# prototype01.net
KiCad netlist of a schematic drawn in EAGLE
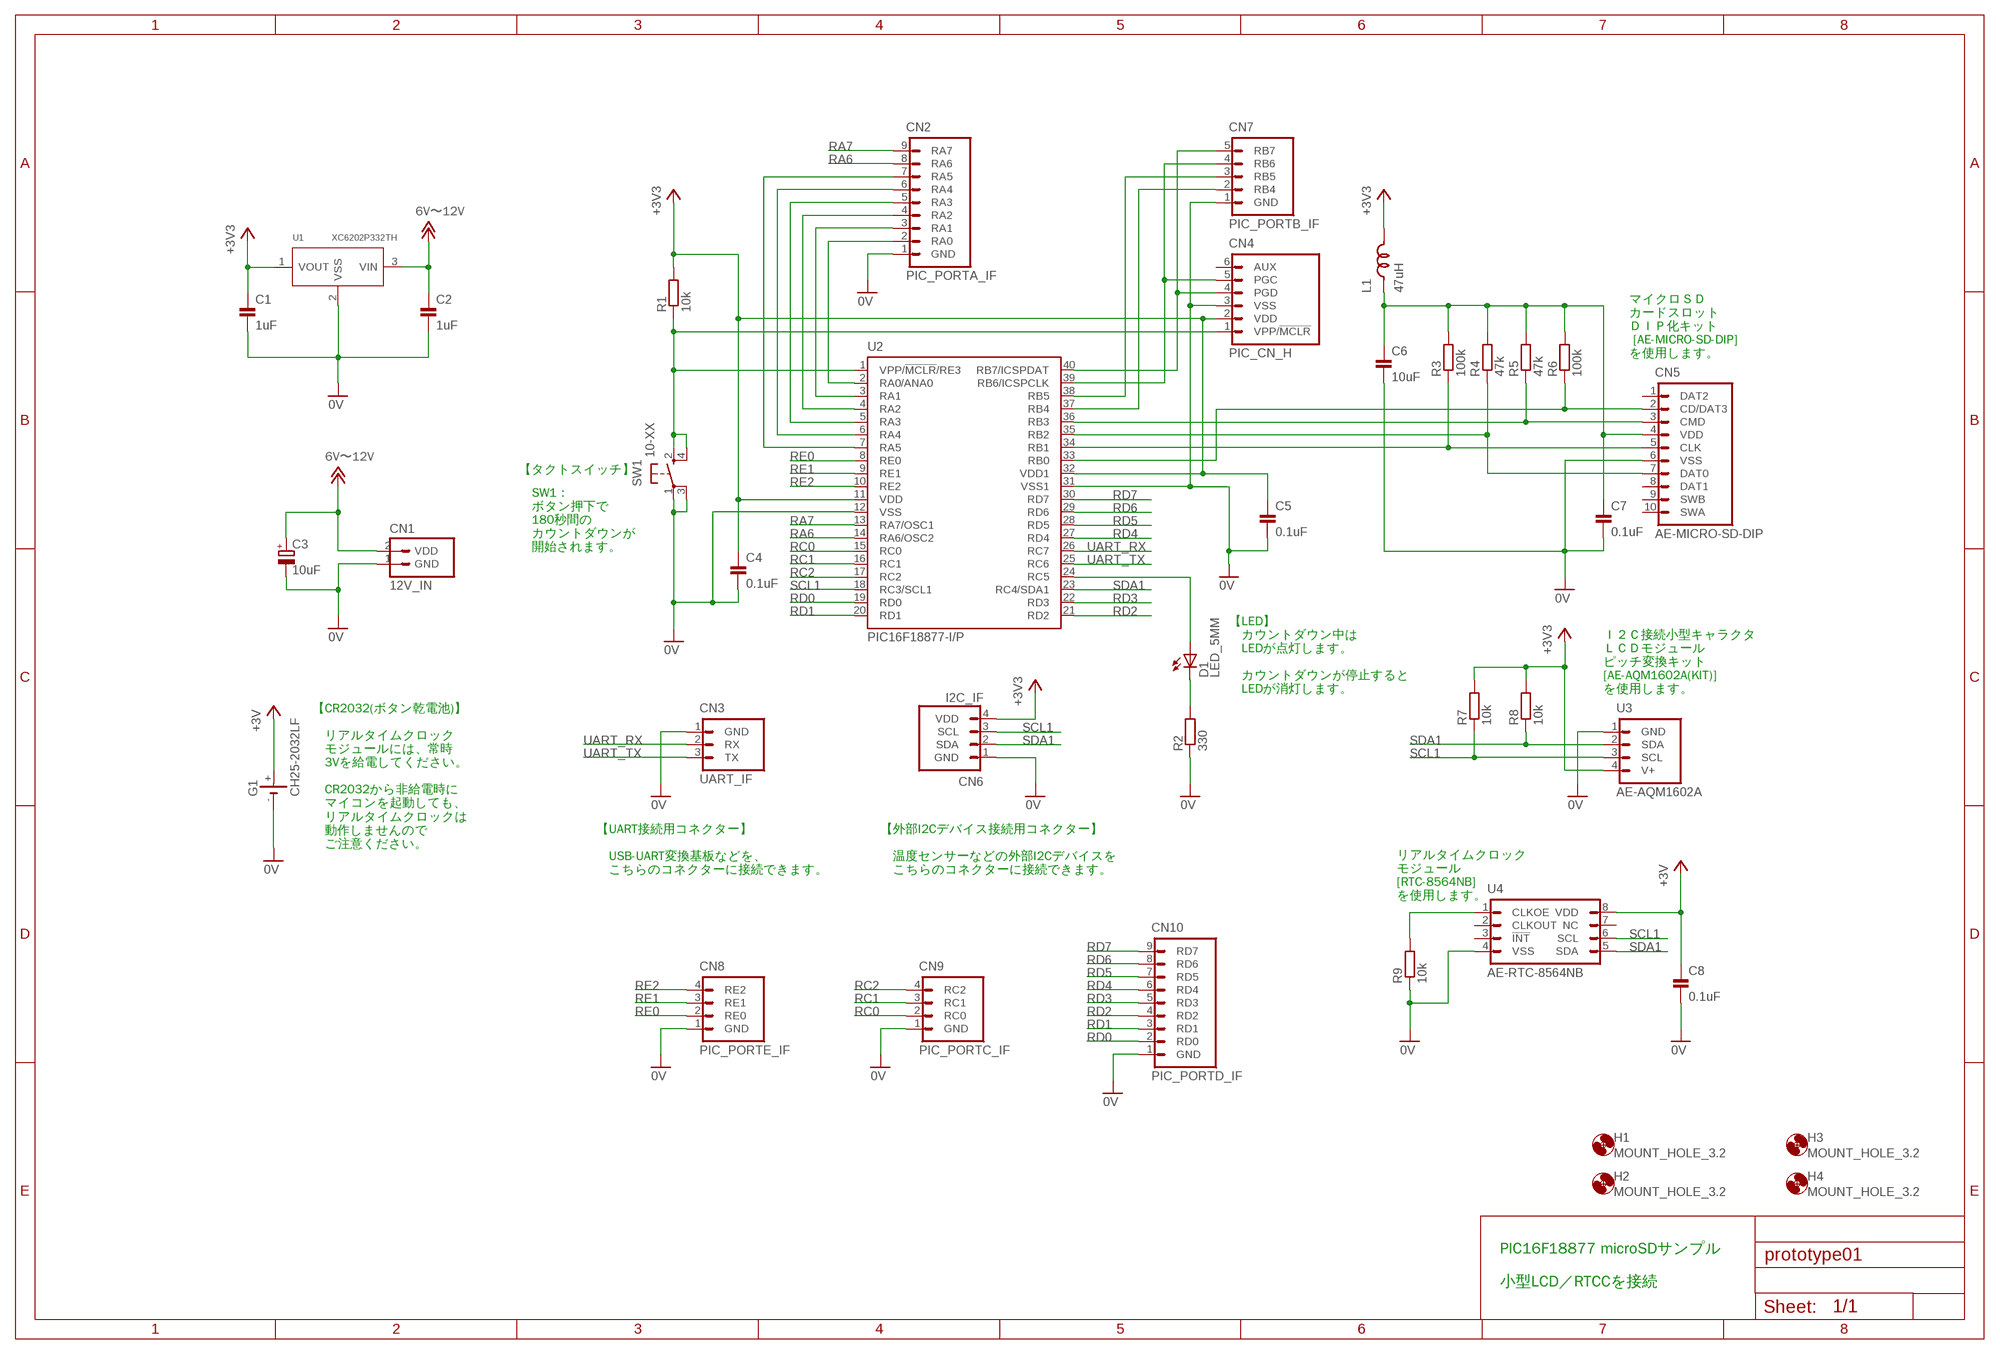
[diagram p0: schematic, sheet 1]

(export (version "E")
  (design (tool "Eeschema 10.0.6"))
  (components
    (comp (ref "C1")
      (value "1uF")
      (footprint "eagle-import:CAP_100MIL")
      (libsource (lib "eagle-import") (part "CAP_100MIL"))
    )
    (comp (ref "C2")
      (value "1uF")
      (footprint "eagle-import:CAP_100MIL")
      (libsource (lib "eagle-import") (part "CAP_100MIL"))
    )
    (comp (ref "C3")
      (value "10uF")
      (footprint "eagle-import:ELECAP_D5_100MIL")
      (libsource (lib "eagle-import") (part "ELECAP_D5_100MIL"))
    )
    (comp (ref "C4")
      (value "0.1uF")
      (footprint "eagle-import:CAP_100MIL")
      (libsource (lib "eagle-import") (part "CAP_100MIL"))
    )
    (comp (ref "C5")
      (value "0.1uF")
      (footprint "eagle-import:CAP_100MIL")
      (libsource (lib "eagle-import") (part "CAP_100MIL"))
    )
    (comp (ref "C6")
      (value "10uF")
      (footprint "eagle-import:CAP_100MIL")
      (libsource (lib "eagle-import") (part "CAP_100MIL"))
    )
    (comp (ref "C7")
      (value "0.1uF")
      (footprint "eagle-import:CAP_100MIL")
      (libsource (lib "eagle-import") (part "CAP_100MIL"))
    )
    (comp (ref "C8")
      (value "0.1uF")
      (footprint "eagle-import:CAP_100MIL")
      (libsource (lib "eagle-import") (part "CAP_100MIL"))
    )
    (comp (ref "CN1")
      (value "12V_IN")
      (footprint "eagle-import:HEADER_2PIN_POWER_IF")
      (libsource (lib "eagle-import") (part "POWER_IF"))
    )
    (comp (ref "CN2")
      (value "PIC_PORTA_IF")
      (footprint "eagle-import:PIC_PORTA_IF_9PIN")
      (libsource (lib "eagle-import") (part "PIC_PORTA_IF"))
    )
    (comp (ref "CN3")
      (value "UART_IF")
      (footprint "eagle-import:UART_IF_3PIN")
      (libsource (lib "eagle-import") (part "UART_IF"))
    )
    (comp (ref "CN4")
      (value "PIC_CN_H")
      (footprint "eagle-import:HEADER_6PIN")
      (libsource (lib "eagle-import") (part "PIC_CN_H"))
    )
    (comp (ref "CN5")
      (value "AE-MICRO-SD-DIP")
      (footprint "eagle-import:AE-MICRO-SD-DIP")
      (libsource (lib "eagle-import") (part "AE-MICRO-SD-DIP"))
    )
    (comp (ref "CN6")
      (value "I2C_IF")
      (footprint "eagle-import:I2C_IF_4PIN")
      (libsource (lib "eagle-import") (part "I2C_IF"))
    )
    (comp (ref "CN7")
      (value "PIC_PORTB_IF")
      (footprint "eagle-import:PIC_PORTB_IF_5PIN")
      (libsource (lib "eagle-import") (part "PIC_PORTB_IF"))
    )
    (comp (ref "CN8")
      (value "PIC_PORTE_IF")
      (footprint "eagle-import:PIC_PORTE_IF_4PIN")
      (libsource (lib "eagle-import") (part "PIC_PORTE_IF"))
    )
    (comp (ref "CN9")
      (value "PIC_PORTC_IF")
      (footprint "eagle-import:PIC_PORTC_IF_4PIN")
      (libsource (lib "eagle-import") (part "PIC_PORTC_IF"))
    )
    (comp (ref "CN10")
      (value "PIC_PORTD_IF")
      (footprint "eagle-import:PIC_PORTD_IF_9PIN")
      (libsource (lib "eagle-import") (part "PIC_PORTD_IF"))
    )
    (comp (ref "D1")
      (value "LED_5MM")
      (footprint "eagle-import:LED5MM")
      (libsource (lib "eagle-import") (part "LED_5MM"))
    )
    (comp (ref "G1")
      (value "CH25-2032LF")
      (footprint "eagle-import:CH25-2032LF")
      (libsource (lib "eagle-import") (part "CH25-2032LF"))
    )
    (comp (ref "H1")
      (value "MOUNT_HOLE_3.2")
      (footprint "eagle-import:3,2")
      (libsource (lib "eagle-import") (part "MOUNT_HOLE_3.2"))
    )
    (comp (ref "H2")
      (value "MOUNT_HOLE_3.2")
      (footprint "eagle-import:3,2")
      (libsource (lib "eagle-import") (part "MOUNT_HOLE_3.2"))
    )
    (comp (ref "H3")
      (value "MOUNT_HOLE_3.2")
      (footprint "eagle-import:3,2")
      (libsource (lib "eagle-import") (part "MOUNT_HOLE_3.2"))
    )
    (comp (ref "H4")
      (value "MOUNT_HOLE_3.2")
      (footprint "eagle-import:3,2")
      (libsource (lib "eagle-import") (part "MOUNT_HOLE_3.2"))
    )
    (comp (ref "L1")
      (value "47uH")
      (footprint "eagle-import:INDUCTOR_0207_300MIL")
      (libsource (lib "eagle-import") (part "LEAD_INDUCTOR"))
    )
    (comp (ref "R1")
      (value "10k")
      (footprint "eagle-import:RESISTOR_0204_200MIL")
      (libsource (lib "eagle-import") (part "RESISTOR_200MIL"))
    )
    (comp (ref "R2")
      (value "330")
      (footprint "eagle-import:RESISTOR_0204_200MIL")
      (libsource (lib "eagle-import") (part "RESISTOR_200MIL"))
    )
    (comp (ref "R3")
      (value "100k")
      (footprint "eagle-import:RESISTOR_0204_200MIL")
      (libsource (lib "eagle-import") (part "RESISTOR_200MIL"))
    )
    (comp (ref "R4")
      (value "47k")
      (footprint "eagle-import:RESISTOR_0204_200MIL")
      (libsource (lib "eagle-import") (part "RESISTOR_200MIL"))
    )
    (comp (ref "R5")
      (value "47k")
      (footprint "eagle-import:RESISTOR_0204_200MIL")
      (libsource (lib "eagle-import") (part "RESISTOR_200MIL"))
    )
    (comp (ref "R6")
      (value "100k")
      (footprint "eagle-import:RESISTOR_0204_200MIL")
      (libsource (lib "eagle-import") (part "RESISTOR_200MIL"))
    )
    (comp (ref "R7")
      (value "10k")
      (footprint "eagle-import:RESISTOR_0204_200MIL")
      (libsource (lib "eagle-import") (part "RESISTOR_200MIL"))
    )
    (comp (ref "R8")
      (value "10k")
      (footprint "eagle-import:RESISTOR_0204_200MIL")
      (libsource (lib "eagle-import") (part "RESISTOR_200MIL"))
    )
    (comp (ref "R9")
      (value "10k")
      (footprint "eagle-import:RESISTOR_0204_200MIL")
      (libsource (lib "eagle-import") (part "RESISTOR_200MIL"))
    )
    (comp (ref "SW1")
      (value "10-XX")
      (footprint "eagle-import:B3F-10XX")
      (libsource (lib "eagle-import") (part "10-XX"))
    )
    (comp (ref "U1")
      (value "XC6202P332TH")
      (footprint "eagle-import:TO92-LINE")
      (libsource (lib "eagle-import") (part "XC6202P332TH"))
    )
    (comp (ref "U2")
      (value "PIC16F18877-I/P")
      (footprint "eagle-import:DIL40")
      (libsource (lib "eagle-import") (part "PIC16F18877-I/P"))
    )
    (comp (ref "U3")
      (value "AE-AQM1602A")
      (footprint "eagle-import:AE-AQM1602A")
      (libsource (lib "eagle-import") (part "AE-AQM1602A"))
    )
    (comp (ref "U4")
      (value "AE-RTC-8564NB")
      (footprint "eagle-import:DIL8_AE-RTC-8564NB")
      (libsource (lib "eagle-import") (part "AE-RTC-8564NB"))
    )
  )
  (nets
    (net (code "1") (name "+3V") (class "Default")
      (node (ref "C8") (pin "1") (pinfunction "1_1") (pintype "passive"))
      (node (ref "G1") (pin "+") (pinfunction "+_+") (pintype "passive"))
      (node (ref "U4") (pin "8") (pinfunction "VDD_8") (pintype "passive"))
    )
    (net (code "2") (name "+3V3") (class "Default")
      (node (ref "C1") (pin "1") (pinfunction "1_1") (pintype "passive"))
      (node (ref "C4") (pin "1") (pinfunction "1_1") (pintype "passive"))
      (node (ref "C5") (pin "1") (pinfunction "1_1") (pintype "passive"))
      (node (ref "CN4") (pin "2") (pinfunction "VDD_2") (pintype "passive"))
      (node (ref "CN6") (pin "4") (pinfunction "VDD_4") (pintype "passive"))
      (node (ref "L1") (pin "2") (pinfunction "2_2") (pintype "passive"))
      (node (ref "R1") (pin "2") (pinfunction "2_2") (pintype "passive"))
      (node (ref "R7") (pin "2") (pinfunction "2_2") (pintype "passive"))
      (node (ref "R8") (pin "2") (pinfunction "2_2") (pintype "passive"))
      (node (ref "U1") (pin "1") (pinfunction "VOUT_1") (pintype "passive"))
      (node (ref "U2") (pin "11") (pinfunction "VDD_11") (pintype "passive"))
      (node (ref "U2") (pin "32") (pinfunction "VDD1_32") (pintype "passive"))
      (node (ref "U3") (pin "4") (pinfunction "V+_4") (pintype "passive"))
    )
    (net (code "3") (name "/RA6") (class "Default")
      (node (ref "CN2") (pin "8") (pinfunction "RA6_8") (pintype "bidirectional"))
      (node (ref "U2") (pin "14") (pinfunction "RA6/OSC2_14") (pintype "bidirectional"))
    )
    (net (code "4") (name "/RA7") (class "Default")
      (node (ref "CN2") (pin "9") (pinfunction "RA7_9") (pintype "bidirectional"))
      (node (ref "U2") (pin "13") (pinfunction "RA7/OSC1_13") (pintype "bidirectional"))
    )
    (net (code "5") (name "/RC0") (class "Default")
      (node (ref "CN9") (pin "2") (pinfunction "RC0_2") (pintype "bidirectional"))
      (node (ref "U2") (pin "15") (pinfunction "RC0_15") (pintype "bidirectional"))
    )
    (net (code "6") (name "/RC1") (class "Default")
      (node (ref "CN9") (pin "3") (pinfunction "RC1_3") (pintype "bidirectional"))
      (node (ref "U2") (pin "16") (pinfunction "RC1_16") (pintype "bidirectional"))
    )
    (net (code "7") (name "/RC2") (class "Default")
      (node (ref "CN9") (pin "4") (pinfunction "RC2_4") (pintype "bidirectional"))
      (node (ref "U2") (pin "17") (pinfunction "RC2_17") (pintype "bidirectional"))
    )
    (net (code "8") (name "/RD0") (class "Default")
      (node (ref "CN10") (pin "2") (pinfunction "RD0_2") (pintype "bidirectional"))
      (node (ref "U2") (pin "19") (pinfunction "RD0_19") (pintype "bidirectional"))
    )
    (net (code "9") (name "/RD1") (class "Default")
      (node (ref "CN10") (pin "3") (pinfunction "RD1_3") (pintype "bidirectional"))
      (node (ref "U2") (pin "20") (pinfunction "RD1_20") (pintype "bidirectional"))
    )
    (net (code "10") (name "/RD2") (class "Default")
      (node (ref "CN10") (pin "4") (pinfunction "RD2_4") (pintype "bidirectional"))
      (node (ref "U2") (pin "21") (pinfunction "RD2_21") (pintype "bidirectional"))
    )
    (net (code "11") (name "/RD3") (class "Default")
      (node (ref "CN10") (pin "5") (pinfunction "RD3_5") (pintype "bidirectional"))
      (node (ref "U2") (pin "22") (pinfunction "RD3_22") (pintype "bidirectional"))
    )
    (net (code "12") (name "/RD4") (class "Default")
      (node (ref "CN10") (pin "6") (pinfunction "RD4_6") (pintype "bidirectional"))
      (node (ref "U2") (pin "27") (pinfunction "RD4_27") (pintype "bidirectional"))
    )
    (net (code "13") (name "/RD5") (class "Default")
      (node (ref "CN10") (pin "7") (pinfunction "RD5_7") (pintype "bidirectional"))
      (node (ref "U2") (pin "28") (pinfunction "RD5_28") (pintype "bidirectional"))
    )
    (net (code "14") (name "/RD6") (class "Default")
      (node (ref "CN10") (pin "8") (pinfunction "RD6_8") (pintype "bidirectional"))
      (node (ref "U2") (pin "29") (pinfunction "RD6_29") (pintype "bidirectional"))
    )
    (net (code "15") (name "/RD7") (class "Default")
      (node (ref "CN10") (pin "9") (pinfunction "RD7_9") (pintype "bidirectional"))
      (node (ref "U2") (pin "30") (pinfunction "RD7_30") (pintype "bidirectional"))
    )
    (net (code "16") (name "/RE0") (class "Default")
      (node (ref "CN8") (pin "2") (pinfunction "RE0_2") (pintype "bidirectional"))
      (node (ref "U2") (pin "8") (pinfunction "RE0_8") (pintype "bidirectional"))
    )
    (net (code "17") (name "/RE1") (class "Default")
      (node (ref "CN8") (pin "3") (pinfunction "RE1_3") (pintype "bidirectional"))
      (node (ref "U2") (pin "9") (pinfunction "RE1_9") (pintype "bidirectional"))
    )
    (net (code "18") (name "/RE2") (class "Default")
      (node (ref "CN8") (pin "4") (pinfunction "RE2_4") (pintype "bidirectional"))
      (node (ref "U2") (pin "10") (pinfunction "RE2_10") (pintype "bidirectional"))
    )
    (net (code "19") (name "/SCL1") (class "Default")
      (node (ref "CN6") (pin "3") (pinfunction "SCL_3") (pintype "bidirectional"))
      (node (ref "R7") (pin "1") (pinfunction "1_1") (pintype "passive"))
      (node (ref "U2") (pin "18") (pinfunction "RC3/SCL1_18") (pintype "bidirectional"))
      (node (ref "U3") (pin "3") (pinfunction "SCL_3") (pintype "bidirectional"))
      (node (ref "U4") (pin "6") (pinfunction "SCL_6") (pintype "bidirectional"))
    )
    (net (code "20") (name "/SDA1") (class "Default")
      (node (ref "CN6") (pin "2") (pinfunction "SDA_2") (pintype "bidirectional"))
      (node (ref "R8") (pin "1") (pinfunction "1_1") (pintype "passive"))
      (node (ref "U2") (pin "23") (pinfunction "RC4/SDA1_23") (pintype "bidirectional"))
      (node (ref "U3") (pin "2") (pinfunction "SDA_2") (pintype "bidirectional"))
      (node (ref "U4") (pin "5") (pinfunction "SDA_5") (pintype "bidirectional"))
    )
    (net (code "21") (name "/UART_RX") (class "Default")
      (node (ref "CN3") (pin "2") (pinfunction "RX_2") (pintype "bidirectional"))
      (node (ref "U2") (pin "26") (pinfunction "RC7_26") (pintype "bidirectional"))
    )
    (net (code "22") (name "/UART_TX") (class "Default")
      (node (ref "CN3") (pin "3") (pinfunction "TX_3") (pintype "bidirectional"))
      (node (ref "U2") (pin "25") (pinfunction "RC6_25") (pintype "bidirectional"))
    )
    (net (code "23") (name "0V") (class "Default")
      (node (ref "C1") (pin "2") (pinfunction "2_2") (pintype "passive"))
      (node (ref "C2") (pin "2") (pinfunction "2_2") (pintype "passive"))
      (node (ref "C3") (pin "-") (pinfunction "-_-") (pintype "passive"))
      (node (ref "C4") (pin "2") (pinfunction "2_2") (pintype "passive"))
      (node (ref "C5") (pin "2") (pinfunction "2_2") (pintype "passive"))
      (node (ref "C6") (pin "2") (pinfunction "2_2") (pintype "passive"))
      (node (ref "C7") (pin "2") (pinfunction "2_2") (pintype "passive"))
      (node (ref "C8") (pin "2") (pinfunction "2_2") (pintype "passive"))
      (node (ref "CN1") (pin "1") (pinfunction "GND_1") (pintype "passive"))
      (node (ref "CN10") (pin "1") (pinfunction "GND_1") (pintype "passive"))
      (node (ref "CN2") (pin "1") (pinfunction "GND_1") (pintype "passive"))
      (node (ref "CN3") (pin "1") (pinfunction "GND_1") (pintype "passive"))
      (node (ref "CN4") (pin "3") (pinfunction "VSS_3") (pintype "passive"))
      (node (ref "CN5") (pin "6") (pinfunction "VSS_6") (pintype "passive"))
      (node (ref "CN6") (pin "1") (pinfunction "GND_1") (pintype "passive"))
      (node (ref "CN7") (pin "1") (pinfunction "GND_1") (pintype "passive"))
      (node (ref "CN8") (pin "1") (pinfunction "GND_1") (pintype "passive"))
      (node (ref "CN9") (pin "1") (pinfunction "GND_1") (pintype "passive"))
      (node (ref "G1") (pin "-") (pinfunction "-_-") (pintype "passive"))
      (node (ref "R2") (pin "1") (pinfunction "1_1") (pintype "passive"))
      (node (ref "R9") (pin "1") (pinfunction "1_1") (pintype "passive"))
      (node (ref "SW1") (pin "1") (pinfunction "P_1") (pintype "passive"))
      (node (ref "SW1") (pin "3") (pinfunction "P1_3") (pintype "passive"))
      (node (ref "U1") (pin "2") (pinfunction "VSS_2") (pintype "passive"))
      (node (ref "U2") (pin "12") (pinfunction "VSS_12") (pintype "passive"))
      (node (ref "U2") (pin "31") (pinfunction "VSS1_31") (pintype "passive"))
      (node (ref "U3") (pin "1") (pinfunction "GND_1") (pintype "passive"))
      (node (ref "U4") (pin "4") (pinfunction "VSS_4") (pintype "passive"))
    )
    (net (code "24") (name "6V〜12V") (class "Default")
      (node (ref "C2") (pin "1") (pinfunction "1_1") (pintype "passive"))
      (node (ref "C3") (pin "+") (pinfunction "+_+") (pintype "passive"))
      (node (ref "CN1") (pin "2") (pinfunction "VDD_2") (pintype "passive"))
      (node (ref "U1") (pin "3") (pinfunction "VIN_3") (pintype "passive"))
    )
    (net (code "25") (name "Net-(CN2-RA0)") (class "Default")
      (node (ref "CN2") (pin "2") (pinfunction "RA0_2") (pintype "bidirectional"))
      (node (ref "U2") (pin "2") (pinfunction "RA0/ANA0_2") (pintype "bidirectional"))
    )
    (net (code "26") (name "Net-(CN2-RA1)") (class "Default")
      (node (ref "CN2") (pin "3") (pinfunction "RA1_3") (pintype "bidirectional"))
      (node (ref "U2") (pin "3") (pinfunction "RA1_3") (pintype "bidirectional"))
    )
    (net (code "27") (name "Net-(CN2-RA2)") (class "Default")
      (node (ref "CN2") (pin "4") (pinfunction "RA2_4") (pintype "bidirectional"))
      (node (ref "U2") (pin "4") (pinfunction "RA2_4") (pintype "bidirectional"))
    )
    (net (code "28") (name "Net-(CN2-RA3)") (class "Default")
      (node (ref "CN2") (pin "5") (pinfunction "RA3_5") (pintype "bidirectional"))
      (node (ref "U2") (pin "5") (pinfunction "RA3_5") (pintype "bidirectional"))
    )
    (net (code "29") (name "Net-(CN2-RA4)") (class "Default")
      (node (ref "CN2") (pin "6") (pinfunction "RA4_6") (pintype "bidirectional"))
      (node (ref "U2") (pin "6") (pinfunction "RA4_6") (pintype "bidirectional"))
    )
    (net (code "30") (name "Net-(CN2-RA5)") (class "Default")
      (node (ref "CN2") (pin "7") (pinfunction "RA5_7") (pintype "bidirectional"))
      (node (ref "U2") (pin "7") (pinfunction "RA5_7") (pintype "bidirectional"))
    )
    (net (code "31") (name "Net-(CN4-PGC)") (class "Default")
      (node (ref "CN4") (pin "5") (pinfunction "PGC_5") (pintype "input"))
      (node (ref "CN7") (pin "4") (pinfunction "RB6_4") (pintype "bidirectional"))
      (node (ref "U2") (pin "39") (pinfunction "RB6/ICSPCLK_39") (pintype "bidirectional"))
    )
    (net (code "32") (name "Net-(CN4-PGD)") (class "Default")
      (node (ref "CN4") (pin "4") (pinfunction "PGD_4") (pintype "bidirectional"))
      (node (ref "CN7") (pin "5") (pinfunction "RB7_5") (pintype "bidirectional"))
      (node (ref "U2") (pin "40") (pinfunction "RB7/ICSPDAT_40") (pintype "bidirectional"))
    )
    (net (code "33") (name "Net-(CN4-VPP{slash}~{MCLR})") (class "Default")
      (node (ref "CN4") (pin "1") (pinfunction "VPP/~{MCLR}_1") (pintype "input"))
      (node (ref "R1") (pin "1") (pinfunction "1_1") (pintype "passive"))
      (node (ref "SW1") (pin "2") (pinfunction "S_2") (pintype "passive"))
      (node (ref "SW1") (pin "4") (pinfunction "S1_4") (pintype "passive"))
      (node (ref "U2") (pin "1") (pinfunction "VPP/~{MCLR}/RE3_1") (pintype "bidirectional"))
    )
    (net (code "34") (name "Net-(CN5-CD{slash}DAT3)") (class "Default")
      (node (ref "CN5") (pin "2") (pinfunction "CD/DAT3_2") (pintype "bidirectional"))
      (node (ref "R6") (pin "1") (pinfunction "1_1") (pintype "passive"))
      (node (ref "U2") (pin "33") (pinfunction "RB0_33") (pintype "bidirectional"))
    )
    (net (code "35") (name "Net-(CN5-CLK)") (class "Default")
      (node (ref "CN5") (pin "5") (pinfunction "CLK_5") (pintype "bidirectional"))
      (node (ref "R3") (pin "1") (pinfunction "1_1") (pintype "passive"))
      (node (ref "U2") (pin "34") (pinfunction "RB1_34") (pintype "bidirectional"))
    )
    (net (code "36") (name "Net-(CN5-CMD)") (class "Default")
      (node (ref "CN5") (pin "3") (pinfunction "CMD_3") (pintype "bidirectional"))
      (node (ref "R5") (pin "1") (pinfunction "1_1") (pintype "passive"))
      (node (ref "U2") (pin "36") (pinfunction "RB3_36") (pintype "bidirectional"))
    )
    (net (code "37") (name "Net-(CN5-DAT0)") (class "Default")
      (node (ref "CN5") (pin "7") (pinfunction "DAT0_7") (pintype "bidirectional"))
      (node (ref "R4") (pin "1") (pinfunction "1_1") (pintype "passive"))
      (node (ref "U2") (pin "35") (pinfunction "RB2_35") (pintype "bidirectional"))
    )
    (net (code "38") (name "Net-(CN5-VDD)") (class "Default")
      (node (ref "C6") (pin "1") (pinfunction "1_1") (pintype "passive"))
      (node (ref "C7") (pin "1") (pinfunction "1_1") (pintype "passive"))
      (node (ref "CN5") (pin "4") (pinfunction "VDD_4") (pintype "passive"))
      (node (ref "L1") (pin "1") (pinfunction "1_1") (pintype "passive"))
      (node (ref "R3") (pin "2") (pinfunction "2_2") (pintype "passive"))
      (node (ref "R4") (pin "2") (pinfunction "2_2") (pintype "passive"))
      (node (ref "R5") (pin "2") (pinfunction "2_2") (pintype "passive"))
      (node (ref "R6") (pin "2") (pinfunction "2_2") (pintype "passive"))
    )
    (net (code "39") (name "Net-(CN7-RB4)") (class "Default")
      (node (ref "CN7") (pin "2") (pinfunction "RB4_2") (pintype "bidirectional"))
      (node (ref "U2") (pin "37") (pinfunction "RB4_37") (pintype "bidirectional"))
    )
    (net (code "40") (name "Net-(CN7-RB5)") (class "Default")
      (node (ref "CN7") (pin "3") (pinfunction "RB5_3") (pintype "bidirectional"))
      (node (ref "U2") (pin "38") (pinfunction "RB5_38") (pintype "bidirectional"))
    )
    (net (code "41") (name "Net-(D1-C)") (class "Default")
      (node (ref "D1") (pin "K") (pinfunction "C_K") (pintype "passive"))
      (node (ref "R2") (pin "2") (pinfunction "2_2") (pintype "passive"))
    )
    (net (code "42") (name "Net-(U2-RC5)") (class "Default")
      (node (ref "D1") (pin "A") (pinfunction "A_A") (pintype "passive"))
      (node (ref "U2") (pin "24") (pinfunction "RC5_24") (pintype "bidirectional"))
    )
    (net (code "43") (name "Net-(U4-CLKOE)") (class "Default")
      (node (ref "R9") (pin "2") (pinfunction "2_2") (pintype "passive"))
      (node (ref "U4") (pin "1") (pinfunction "CLKOE_1") (pintype "bidirectional"))
    )
    (net (code "44") (name "unconnected-(CN4-AUX-Pad6)") (class "Default")
      (node (ref "CN4") (pin "6") (pinfunction "AUX_6") (pintype "bidirectional"))
    )
    (net (code "45") (name "unconnected-(CN5-DAT1-Pad8)") (class "Default")
      (node (ref "CN5") (pin "8") (pinfunction "DAT1_8") (pintype "bidirectional"))
    )
    (net (code "46") (name "unconnected-(CN5-DAT2-Pad1)") (class "Default")
      (node (ref "CN5") (pin "1") (pinfunction "DAT2_1") (pintype "bidirectional"))
    )
    (net (code "47") (name "unconnected-(CN5-SWA-Pad10)") (class "Default")
      (node (ref "CN5") (pin "10") (pinfunction "SWA_10") (pintype "bidirectional"))
    )
    (net (code "48") (name "unconnected-(CN5-SWB-Pad9)") (class "Default")
      (node (ref "CN5") (pin "9") (pinfunction "SWB_9") (pintype "bidirectional"))
    )
    (net (code "49") (name "unconnected-(U4-CLKOUT-Pad2)") (class "Default")
      (node (ref "U4") (pin "2") (pinfunction "CLKOUT_2") (pintype "bidirectional"))
    )
    (net (code "50") (name "unconnected-(U4-NC-Pad7)") (class "Default")
      (node (ref "U4") (pin "7") (pinfunction "NC_7") (pintype "no_connect"))
    )
    (net (code "51") (name "unconnected-(U4-~{INT}-Pad3)") (class "Default")
      (node (ref "U4") (pin "3") (pinfunction "~{INT}_3") (pintype "bidirectional"))
    )
  )
)
